# SlowDAC.net
KiCad netlist of a schematic drawn in Altium Designer
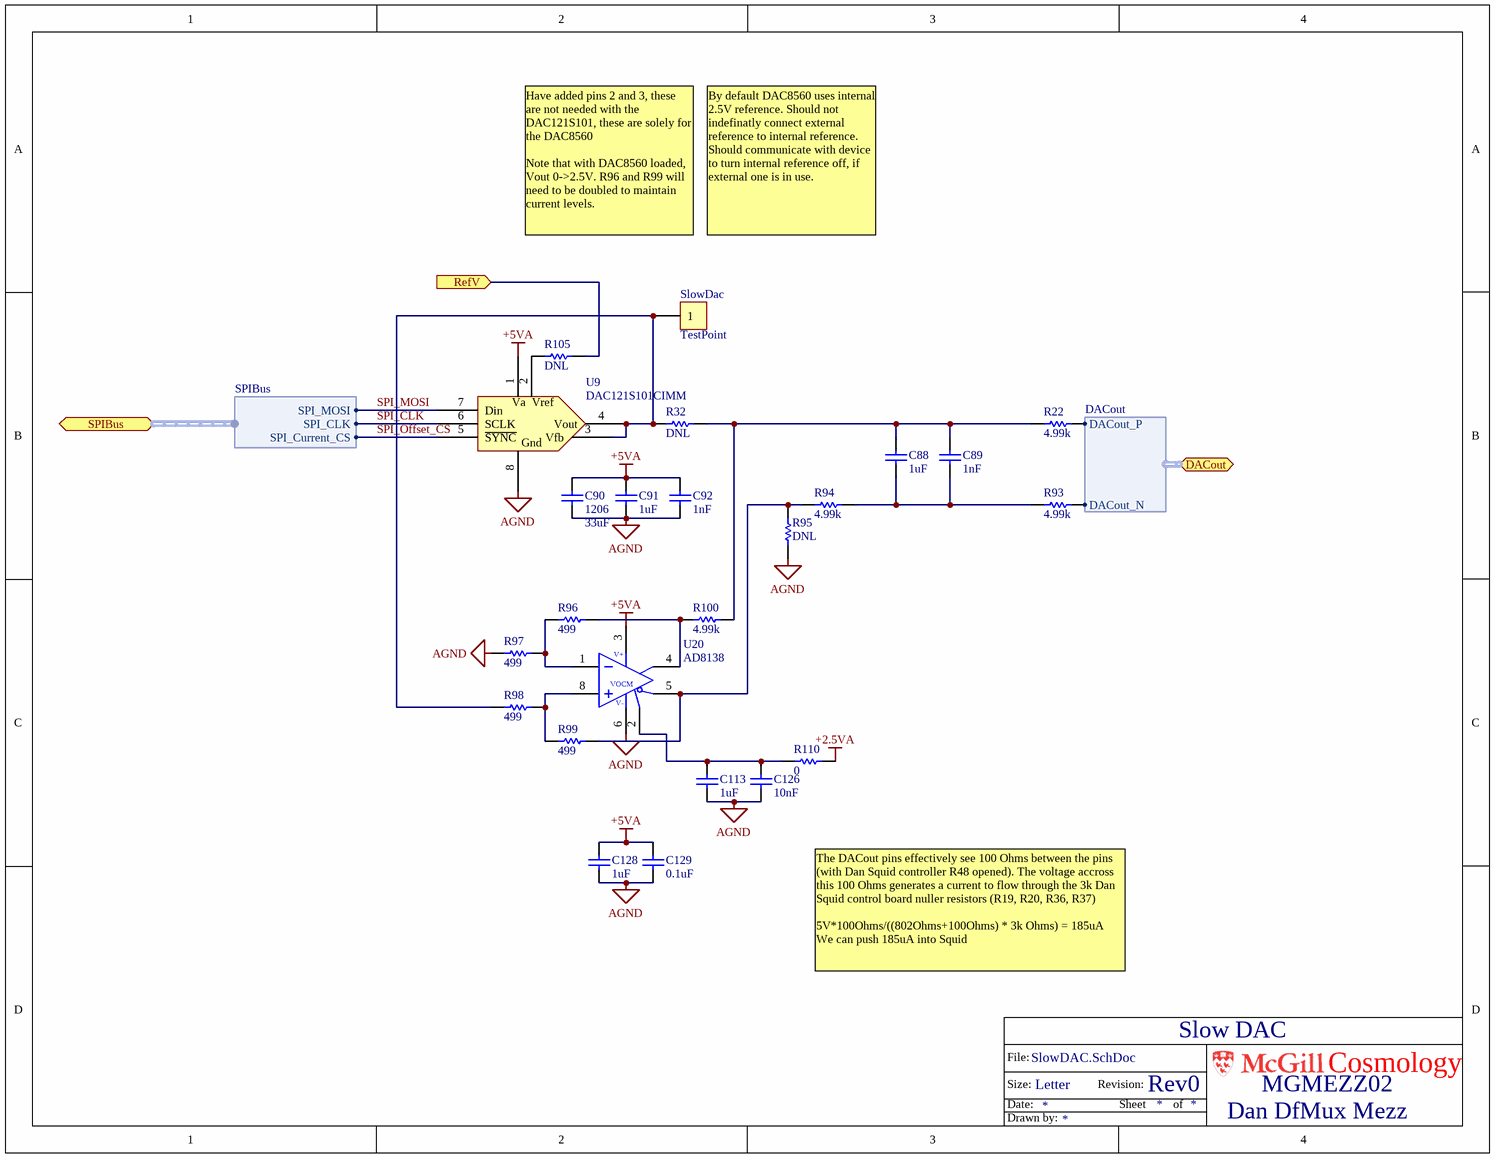
[diagram p0: SlowDAC.SchDoc]

(export (version "E")
  (design (tool "Eeschema 10.0.6"))
  (components
    (comp (ref "C88")
      (value "1uF")
      (footprint "0603")
      (description "Capacitor, Ceramic, 0603")
      (fields
        (field (name "MANUFACTURER") "Generic")
        (field (name "MANUFACTURERS PART NUMBER") "e.g C1608X7R1C105K")
      )
      (libsource (lib "MGMEZZ04") (part "CAP 0603"))
    )
    (comp (ref "C89")
      (value "1nF")
      (footprint "0603")
      (description "Capacitor, Ceramic, 0603")
      (fields (field (name "MANUFACTURER") "Generic"))
      (libsource (lib "MGMEZZ04") (part "CAP 0603"))
    )
    (comp (ref "C90")
      (value "33uF")
      (footprint "1206")
      (description "Capacitor, Ceramic, 1210")
      (fields
        (field (name "MANUFACTURER") "TDK Corporation")
        (field (name "MANUFACTURERS PART NUMBER") "C3216X5R1E336M")
      )
      (libsource (lib "MGMEZZ04") (part "CAP 1210"))
    )
    (comp (ref "C91")
      (value "1uF")
      (footprint "0603")
      (description "Capacitor, Ceramic, 0603")
      (fields
        (field (name "MANUFACTURER") "Generic")
        (field (name "MANUFACTURERS PART NUMBER") "e.g C1608X7R1C105K")
      )
      (libsource (lib "MGMEZZ04") (part "CAP 0603"))
    )
    (comp (ref "C92")
      (value "1nF")
      (footprint "0603")
      (description "Capacitor, Ceramic, 0603")
      (fields (field (name "MANUFACTURER") "Generic"))
      (libsource (lib "MGMEZZ04") (part "CAP 0603"))
    )
    (comp (ref "C113")
      (value "1uF")
      (footprint "0603")
      (description "Capacitor, Ceramic, 0603")
      (fields
        (field (name "MANUFACTURER") "Generic")
        (field (name "MANUFACTURERS PART NUMBER") "e.g C1608X7R1C105K")
      )
      (libsource (lib "MGMEZZ04") (part "CAP 0603"))
    )
    (comp (ref "C126")
      (value "10nF")
      (footprint "0603")
      (description "Capacitor, Ceramic, 0603")
      (fields (field (name "MANUFACTURER") "Generic"))
      (libsource (lib "MGMEZZ04") (part "CAP 0603"))
    )
    (comp (ref "C128")
      (value "1uF")
      (footprint "0603")
      (description "Capacitor, Ceramic, 0603")
      (fields
        (field (name "MANUFACTURER") "Generic")
        (field (name "MANUFACTURERS PART NUMBER") "e.g C1608X7R1C105K")
      )
      (libsource (lib "MGMEZZ04") (part "CAP 0603"))
    )
    (comp (ref "C129")
      (value "0.1uF")
      (footprint "0603")
      (description "Capacitor, Ceramic, 0603")
      (fields (field (name "MANUFACTURER") "Generic"))
      (libsource (lib "MGMEZZ04") (part "CAP 0603"))
    )
    (comp (ref "R22")
      (value "4.99k")
      (footprint "0603")
      (description "Resistor")
      (fields (field (name "MANUFACTURER") "Generic"))
      (libsource (lib "MGMEZZ04") (part "RES 0603"))
    )
    (comp (ref "R32")
      (value "DNL")
      (footprint "0603")
      (description "Resistor")
      (fields (field (name "MANUFACTURER") "Generic"))
      (libsource (lib "MGMEZZ04") (part "RES 0603"))
    )
    (comp (ref "R93")
      (value "4.99k")
      (footprint "0603")
      (description "Resistor")
      (fields (field (name "MANUFACTURER") "Generic"))
      (libsource (lib "MGMEZZ04") (part "RES 0603"))
    )
    (comp (ref "R94")
      (value "4.99k")
      (footprint "0603")
      (description "Resistor")
      (fields (field (name "MANUFACTURER") "Generic"))
      (libsource (lib "MGMEZZ04") (part "RES 0603"))
    )
    (comp (ref "R95")
      (value "DNL")
      (footprint "0603")
      (description "Resistor")
      (fields (field (name "MANUFACTURER") "Generic"))
      (libsource (lib "MGMEZZ04") (part "RES 0603"))
    )
    (comp (ref "R96")
      (value "499")
      (footprint "0603")
      (description "Resistor")
      (fields (field (name "MANUFACTURER") "Generic"))
      (libsource (lib "MGMEZZ04") (part "RES 0603"))
    )
    (comp (ref "R97")
      (value "499")
      (footprint "0603")
      (description "Resistor")
      (fields (field (name "MANUFACTURER") "Generic"))
      (libsource (lib "MGMEZZ04") (part "RES 0603"))
    )
    (comp (ref "R98")
      (value "499")
      (footprint "0603")
      (description "Resistor")
      (fields (field (name "MANUFACTURER") "Generic"))
      (libsource (lib "MGMEZZ04") (part "RES 0603"))
    )
    (comp (ref "R99")
      (value "499")
      (footprint "0603")
      (description "Resistor")
      (fields (field (name "MANUFACTURER") "Generic"))
      (libsource (lib "MGMEZZ04") (part "RES 0603"))
    )
    (comp (ref "R100")
      (value "4.99k")
      (footprint "0603")
      (description "Resistor")
      (fields (field (name "MANUFACTURER") "Generic"))
      (libsource (lib "MGMEZZ04") (part "RES 0603"))
    )
    (comp (ref "R105")
      (value "DNL")
      (footprint "0603")
      (description "Resistor")
      (fields (field (name "MANUFACTURER") "Generic"))
      (libsource (lib "MGMEZZ04") (part "RES 0603"))
    )
    (comp (ref "R110")
      (value "0")
      (footprint "0603")
      (description "Resistor")
      (fields (field (name "MANUFACTURER") "Generic"))
      (libsource (lib "MGMEZZ04") (part "RES 0603"))
    )
    (comp (ref "SlowDac")
      (value "TestPoint")
      (footprint "TP-3520-SK")
      (description "TestPoint1")
      (libsource (lib "MGMEZZ04") (part "TestPoint"))
    )
    (comp (ref "U9")
      (value "DAC121S101CIMM")
      (footprint "MSOP-8")
      (description "CONV D/A 12BIT MICROPWR 8MSOP")
      (fields
        (field (name "MANUFACTURER") "National Semiconductor")
        (field (name "MANUFACTURERS PART NUMBER") "DAC121S101CIMM/NOPB")
      )
      (libsource (lib "MGMEZZ04") (part "DAC121S101CIMM/NOPB"))
    )
    (comp (ref "U20")
      (value "AD8138")
      (footprint "SO8")
      (description "IC AMP DIFF LDIST LP 95MA 8SOIC")
      (fields
        (field (name "MANUFACTURER") "Analog Devices Inc")
        (field (name "MANUFACTURERS PART NUMBER") "AD8138ARZ")
      )
      (libsource (lib "MGMEZZ04") (part "AD8138"))
    )
  )
  (nets
    (net (code "3") (name "+2.5VA") (class "Default")
      (node (ref "R110") (pin "1") (pinfunction "1_1") (pintype "passive"))
    )
    (net (code "4") (name "+5VA") (class "Default")
      (node (ref "C128") (pin "2") (pinfunction "2_2") (pintype "passive"))
      (node (ref "C129") (pin "1") (pinfunction "1_1") (pintype "passive"))
      (node (ref "C90") (pin "2") (pinfunction "2_2") (pintype "passive"))
      (node (ref "C91") (pin "2") (pinfunction "2_2") (pintype "passive"))
      (node (ref "C92") (pin "2") (pinfunction "2_2") (pintype "passive"))
      (node (ref "U20") (pin "3") (pinfunction "V+_3") (pintype "power_in"))
      (node (ref "U9") (pin "1") (pinfunction "Va_1") (pintype "passive"))
    )
    (net (code "5") (name "/DACout_N") (class "Default")
      (node (ref "R93") (pin "1") (pinfunction "1_1") (pintype "passive"))
    )
    (net (code "6") (name "/DACout_P") (class "Default")
      (node (ref "R22") (pin "1") (pinfunction "1_1") (pintype "passive"))
    )
    (net (code "7") (name "/RefV") (class "Default")
      (node (ref "R105") (pin "2") (pinfunction "2_2") (pintype "passive"))
    )
    (net (code "8") (name "/SPI_CLK") (class "Default")
      (node (ref "U9") (pin "6") (pinfunction "SCLK_6") (pintype "passive"))
    )
    (net (code "9") (name "/SPI_MOSI") (class "Default")
      (node (ref "U9") (pin "7") (pinfunction "Din_7") (pintype "passive"))
    )
    (net (code "10") (name "/SPI_Offset_CS") (class "Default")
      (node (ref "U9") (pin "5") (pinfunction "~{SYNC}_5") (pintype "passive"))
    )
    (net (code "13") (name "AGND") (class "Default")
      (node (ref "C113") (pin "1") (pinfunction "1_1") (pintype "passive"))
      (node (ref "C126") (pin "1") (pinfunction "1_1") (pintype "passive"))
      (node (ref "C128") (pin "1") (pinfunction "1_1") (pintype "passive"))
      (node (ref "C129") (pin "2") (pinfunction "2_2") (pintype "passive"))
      (node (ref "C90") (pin "1") (pinfunction "1_1") (pintype "passive"))
      (node (ref "C91") (pin "1") (pinfunction "1_1") (pintype "passive"))
      (node (ref "C92") (pin "1") (pinfunction "1_1") (pintype "passive"))
      (node (ref "R95") (pin "2") (pinfunction "2_2") (pintype "passive"))
      (node (ref "R97") (pin "2") (pinfunction "2_2") (pintype "passive"))
      (node (ref "U20") (pin "6") (pinfunction "V-_6") (pintype "power_in"))
      (node (ref "U9") (pin "8") (pinfunction "Gnd_8") (pintype "passive"))
    )
    (net (code "14") (name "Net-(C88-Pad1)") (class "Default")
      (node (ref "C88") (pin "1") (pinfunction "1_1") (pintype "passive"))
      (node (ref "C89") (pin "1") (pinfunction "1_1") (pintype "passive"))
      (node (ref "R93") (pin "2") (pinfunction "2_2") (pintype "passive"))
      (node (ref "R94") (pin "1") (pinfunction "1_1") (pintype "passive"))
    )
    (net (code "15") (name "Net-(C88-Pad2)") (class "Default")
      (node (ref "C88") (pin "2") (pinfunction "2_2") (pintype "passive"))
      (node (ref "C89") (pin "2") (pinfunction "2_2") (pintype "passive"))
      (node (ref "R100") (pin "1") (pinfunction "1_1") (pintype "passive"))
      (node (ref "R22") (pin "2") (pinfunction "2_2") (pintype "passive"))
      (node (ref "R32") (pin "1") (pinfunction "1_1") (pintype "passive"))
    )
    (net (code "16") (name "Net-(U9-Vfb)") (class "Default")
      (node (ref "R32") (pin "2") (pinfunction "2_2") (pintype "passive"))
      (node (ref "R98") (pin "2") (pinfunction "2_2") (pintype "passive"))
      (node (ref "SlowDac") (pin "1") (pinfunction "1_1") (pintype "passive"))
      (node (ref "U9") (pin "3") (pinfunction "Vfb_3") (pintype "passive"))
      (node (ref "U9") (pin "4") (pinfunction "Vout_4") (pintype "passive"))
    )
    (net (code "17") (name "Net-(U9-Vref)") (class "Default")
      (node (ref "R105") (pin "1") (pinfunction "1_1") (pintype "passive"))
      (node (ref "U9") (pin "2") (pinfunction "Vref_2") (pintype "passive"))
    )
    (net (code "18") (name "Net-(U20-IN+)") (class "Default")
      (node (ref "R98") (pin "1") (pinfunction "1_1") (pintype "passive"))
      (node (ref "R99") (pin "2") (pinfunction "2_2") (pintype "passive"))
      (node (ref "U20") (pin "8") (pinfunction "IN+_8") (pintype "passive"))
    )
    (net (code "19") (name "Net-(U20-IN-)") (class "Default")
      (node (ref "R96") (pin "2") (pinfunction "2_2") (pintype "passive"))
      (node (ref "R97") (pin "1") (pinfunction "1_1") (pintype "passive"))
      (node (ref "U20") (pin "1") (pinfunction "IN-_1") (pintype "passive"))
    )
    (net (code "20") (name "Net-(U20-OUT+)") (class "Default")
      (node (ref "R100") (pin "2") (pinfunction "2_2") (pintype "passive"))
      (node (ref "R96") (pin "1") (pinfunction "1_1") (pintype "passive"))
      (node (ref "U20") (pin "4") (pinfunction "OUT+_4") (pintype "passive"))
    )
    (net (code "21") (name "Net-(U20-OUT-)") (class "Default")
      (node (ref "R94") (pin "2") (pinfunction "2_2") (pintype "passive"))
      (node (ref "R95") (pin "1") (pinfunction "1_1") (pintype "passive"))
      (node (ref "R99") (pin "1") (pinfunction "1_1") (pintype "passive"))
      (node (ref "U20") (pin "5") (pinfunction "OUT-_5") (pintype "passive"))
    )
    (net (code "22") (name "Net-(U20-VOCM)") (class "Default")
      (node (ref "C113") (pin "2") (pinfunction "2_2") (pintype "passive"))
      (node (ref "C126") (pin "2") (pinfunction "2_2") (pintype "passive"))
      (node (ref "R110") (pin "2") (pinfunction "2_2") (pintype "passive"))
      (node (ref "U20") (pin "2") (pinfunction "VOCM_2") (pintype "passive"))
    )
    (net (code "23") (name "unconnected-(U9-NC-Pad2)") (class "Default")
      (node (ref "U9") (pin "2") (pinfunction "NC_2") (pintype "passive"))
    )
    (net (code "24") (name "unconnected-(U9-NC-Pad3)") (class "Default")
      (node (ref "U9") (pin "3") (pinfunction "NC_3") (pintype "passive"))
    )
    (net (code "25") (name "unconnected-(U20-NC-Pad7)") (class "Default")
      (node (ref "U20") (pin "7") (pinfunction "NC_7") (pintype "passive"))
    )
  )
)
